# PCB-DISPLAYDOGM1.net
KiCad netlist of a schematic drawn in EAGLE
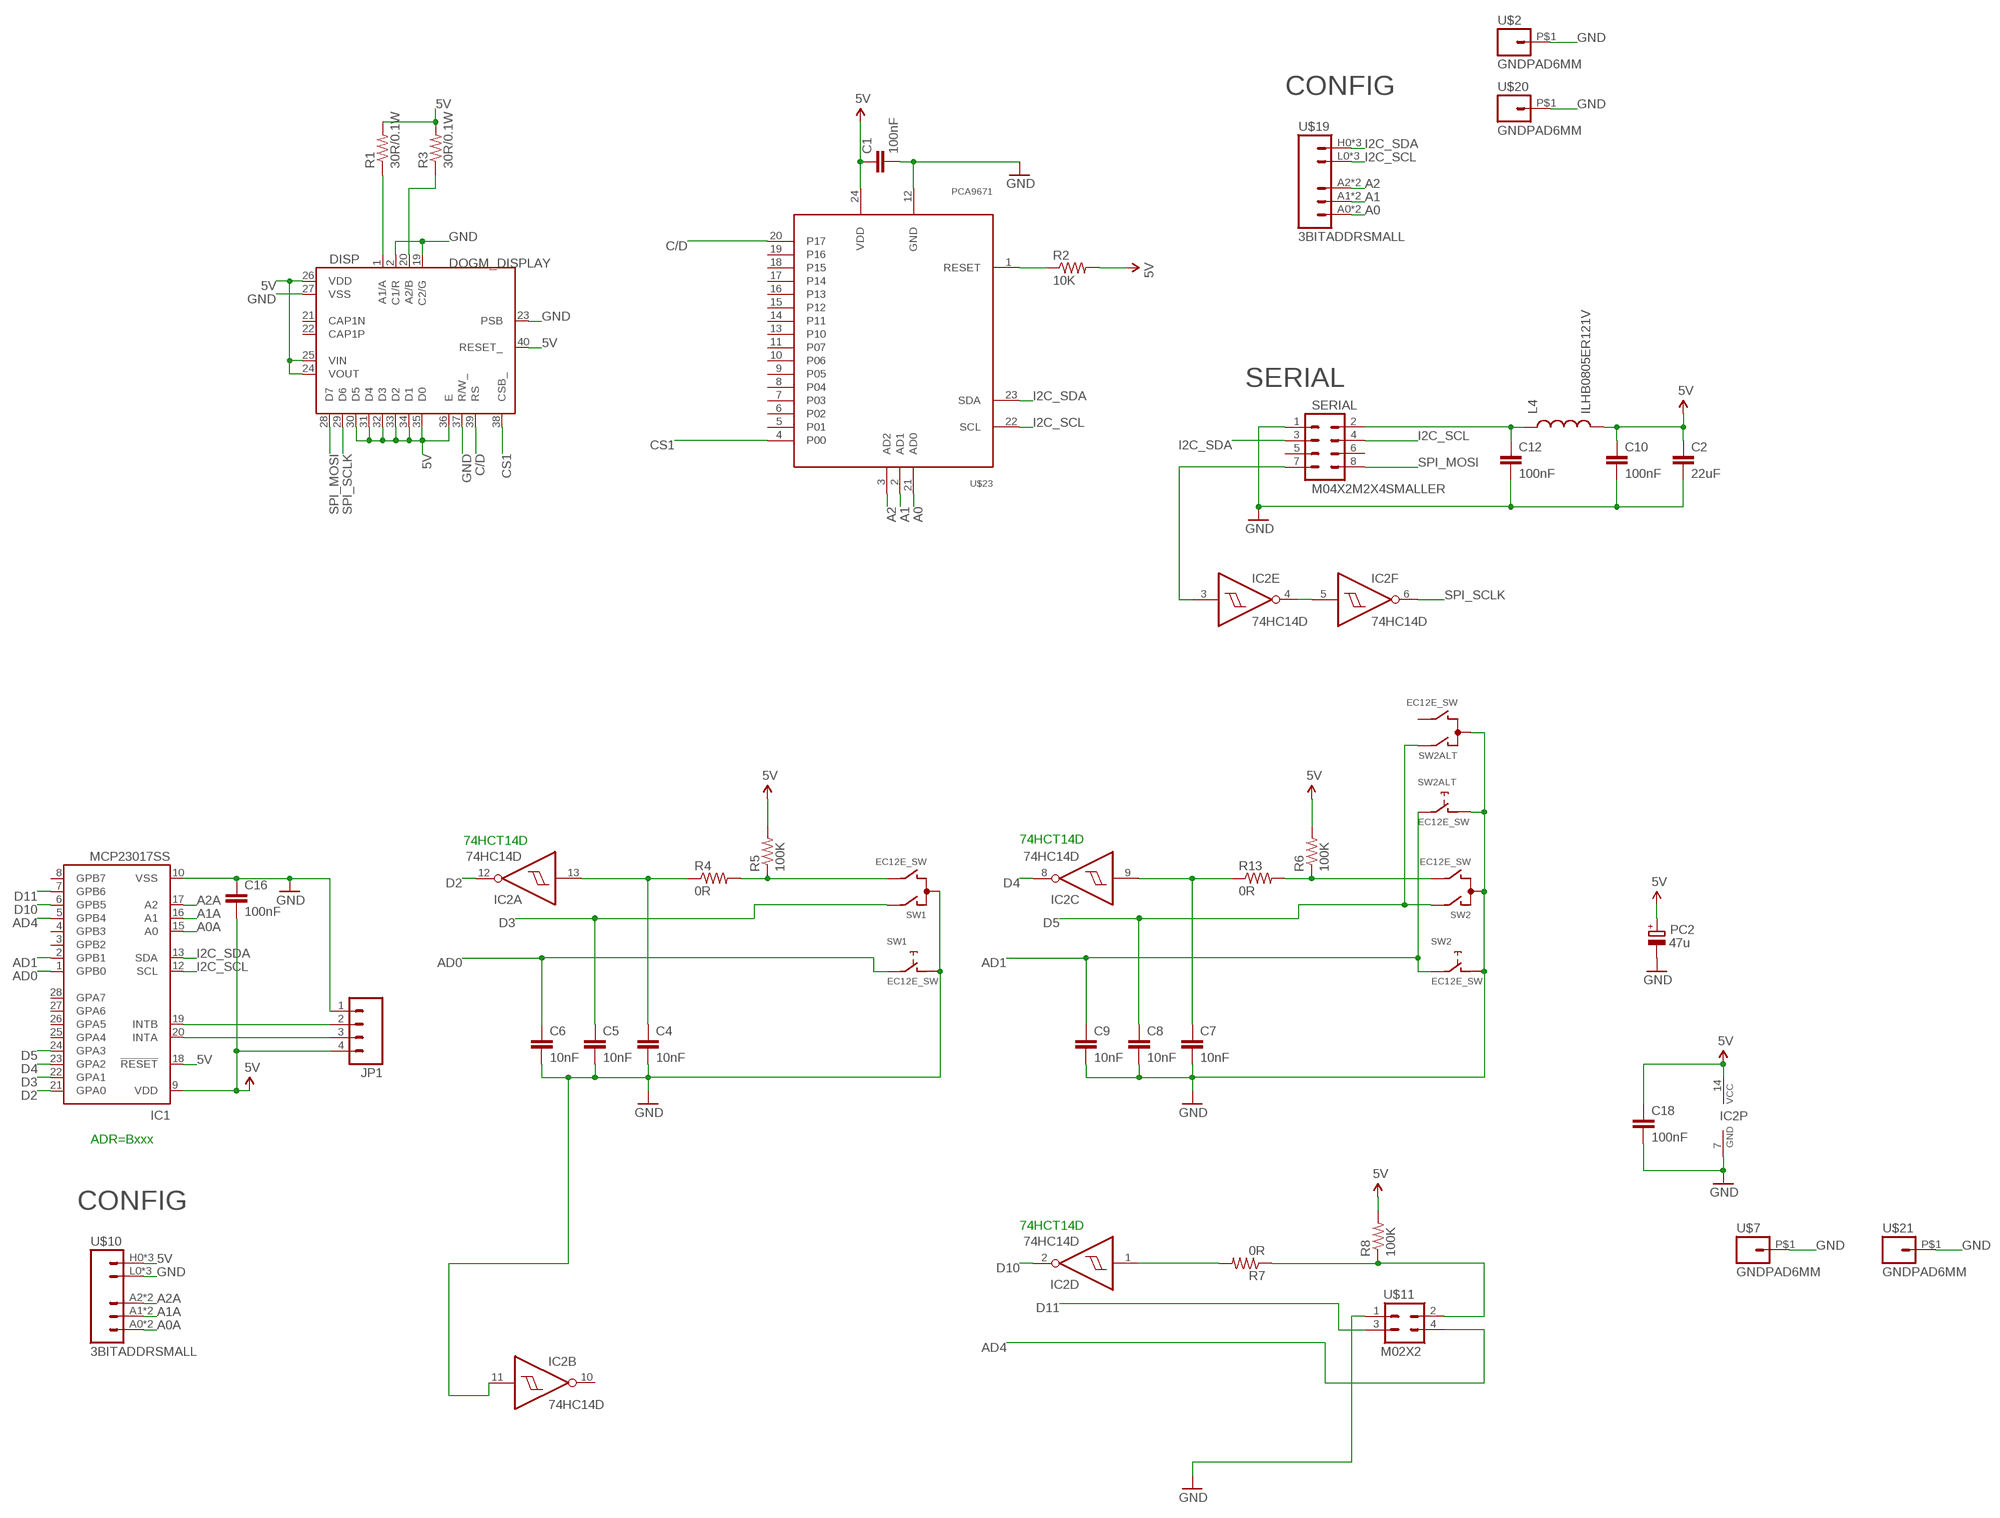
[diagram p0: schematic, sheet 1]

(export (version "E")
  (design (tool "Eeschema 10.0.6"))
  (components
    (comp (ref "C1")
      (value "100nF")
      (footprint "eagle-import:0603-CAP")
      (libsource (lib "eagle-import") (part "CAP0603-CAP"))
    )
    (comp (ref "C2")
      (value "22uF")
      (footprint "eagle-import:0805")
      (libsource (lib "eagle-import") (part "CAP0805"))
    )
    (comp (ref "C4")
      (value "10nF")
      (footprint "eagle-import:0603-CAP")
      (libsource (lib "eagle-import") (part "CAP0603-CAP"))
    )
    (comp (ref "C5")
      (value "10nF")
      (footprint "eagle-import:0603-CAP")
      (libsource (lib "eagle-import") (part "CAP0603-CAP"))
    )
    (comp (ref "C6")
      (value "10nF")
      (footprint "eagle-import:0603-CAP")
      (libsource (lib "eagle-import") (part "CAP0603-CAP"))
    )
    (comp (ref "C7")
      (value "10nF")
      (footprint "eagle-import:0603-CAP")
      (libsource (lib "eagle-import") (part "CAP0603-CAP"))
    )
    (comp (ref "C8")
      (value "10nF")
      (footprint "eagle-import:0603-CAP")
      (libsource (lib "eagle-import") (part "CAP0603-CAP"))
    )
    (comp (ref "C9")
      (value "10nF")
      (footprint "eagle-import:0603-CAP")
      (libsource (lib "eagle-import") (part "CAP0603-CAP"))
    )
    (comp (ref "C10")
      (value "100nF")
      (footprint "eagle-import:0603-CAP")
      (libsource (lib "eagle-import") (part "CAP0603-CAP"))
    )
    (comp (ref "C12")
      (value "100nF")
      (footprint "eagle-import:0603-CAP")
      (libsource (lib "eagle-import") (part "CAP0603-CAP"))
    )
    (comp (ref "C16")
      (value "100nF")
      (footprint "eagle-import:0603-CAP")
      (libsource (lib "eagle-import") (part "CAP0603-CAP"))
    )
    (comp (ref "C18")
      (value "100nF")
      (footprint "eagle-import:0603-CAP")
      (libsource (lib "eagle-import") (part "CAP0603-CAP"))
    )
    (comp (ref "DISP")
      (value "DOGM_DISPLAY")
      (footprint "eagle-import:DOGM")
      (libsource (lib "eagle-import") (part "DOGM_DISPLAY"))
    )
    (comp (ref "IC1")
      (value "MCP23017SS")
      (footprint "eagle-import:SSOP28")
      (fields
        (field (name "MF") "MICROCHIP")
        (field (name "MPN") "MCP23017-E/SS")
        (field (name "MPN_1") "MCP23017-E/SS")
        (field (name "OC_FARNELL") "1467674")
        (field (name "OC_NEWARK") "31K2960")
      )
      (libsource (lib "eagle-import") (part "MCP23017SS"))
    )
    (comp (ref "IC2")
      (value "74HC14D")
      (footprint "eagle-import:SO14")
      (libsource (lib "eagle-import") (part "7414DHC"))
    )
    (comp (ref "JP1")
      (value "M04PTH")
      (footprint "eagle-import:1X04")
      (libsource (lib "eagle-import") (part "M04PTH"))
    )
    (comp (ref "L4")
      (value "ILHB0805ER121V")
      (footprint "eagle-import:0805")
      (libsource (lib "eagle-import") (part "INDUCTOR0805"))
    )
    (comp (ref "PC2")
      (value "47u")
      (footprint "eagle-import:PANASONIC_D")
      (libsource (lib "eagle-import") (part "CPOL-EUD"))
    )
    (comp (ref "R1")
      (value "30R/0.1W")
      (footprint "eagle-import:0603-RES")
      (libsource (lib "eagle-import") (part "RESISTOR0603-RES"))
    )
    (comp (ref "R2")
      (value "10K")
      (footprint "eagle-import:0603-RES")
      (libsource (lib "eagle-import") (part "RESISTOR0603-RES"))
    )
    (comp (ref "R3")
      (value "30R/0.1W")
      (footprint "eagle-import:0603-RES")
      (libsource (lib "eagle-import") (part "RESISTOR0603-RES"))
    )
    (comp (ref "R4")
      (value "0R")
      (footprint "eagle-import:0603-RES")
      (libsource (lib "eagle-import") (part "RESISTOR0603-RES"))
    )
    (comp (ref "R5")
      (value "100K")
      (footprint "eagle-import:0603-RES")
      (libsource (lib "eagle-import") (part "RESISTOR0603-RES"))
    )
    (comp (ref "R6")
      (value "100K")
      (footprint "eagle-import:0603-RES")
      (libsource (lib "eagle-import") (part "RESISTOR0603-RES"))
    )
    (comp (ref "R7")
      (value "0R")
      (footprint "eagle-import:0603-RES")
      (libsource (lib "eagle-import") (part "RESISTOR0603-RES"))
    )
    (comp (ref "R8")
      (value "100K")
      (footprint "eagle-import:0603-RES")
      (libsource (lib "eagle-import") (part "RESISTOR0603-RES"))
    )
    (comp (ref "R13")
      (value "0R")
      (footprint "eagle-import:0603-RES")
      (libsource (lib "eagle-import") (part "RESISTOR0603-RES"))
    )
    (comp (ref "SERIAL")
      (value "M04X2M2X4SMALLER")
      (footprint "eagle-import:M2X4SMALLER")
      (libsource (lib "eagle-import") (part "M04X2M2X4SMALLER"))
    )
    (comp (ref "SW1")
      (value "EC12E_SW")
      (footprint "eagle-import:ALPS_EC12E_SW")
      (fields (field (name "MPN") "EC12E2424407"))
      (libsource (lib "eagle-import") (part "EC12E_SW"))
    )
    (comp (ref "SW2")
      (value "EC12E_SW")
      (footprint "eagle-import:ALPS_EC12E_SW")
      (fields (field (name "MPN") "EC12E2424407"))
      (libsource (lib "eagle-import") (part "EC12E_SW"))
    )
    (comp (ref "SW2ALT")
      (value "EC12E_SW")
      (footprint "eagle-import:ALPS_EC12E_SW")
      (fields (field (name "MPN") "EC12E2424407"))
      (libsource (lib "eagle-import") (part "EC12E_SW"))
    )
    (comp (ref "U$2")
      (value "GNDPAD6MM")
      (footprint "eagle-import:3.2MMPAD6MM")
      (libsource (lib "eagle-import") (part "GNDPAD6MM"))
    )
    (comp (ref "U$7")
      (value "GNDPAD6MM")
      (footprint "eagle-import:3.2MMPAD6MM")
      (libsource (lib "eagle-import") (part "GNDPAD6MM"))
    )
    (comp (ref "U$10")
      (value "3BITADDRSMALL")
      (footprint "eagle-import:3BITADDR_SMALL")
      (libsource (lib "eagle-import") (part "3BITADDRSMALL"))
    )
    (comp (ref "U$11")
      (value "M02X2")
      (footprint "eagle-import:2X2")
      (libsource (lib "eagle-import") (part "M02X2"))
    )
    (comp (ref "U$19")
      (value "3BITADDRSMALL")
      (footprint "eagle-import:3BITADDR_SMALL")
      (libsource (lib "eagle-import") (part "3BITADDRSMALL"))
    )
    (comp (ref "U$20")
      (value "GNDPAD6MM")
      (footprint "eagle-import:3.2MMPAD6MM")
      (libsource (lib "eagle-import") (part "GNDPAD6MM"))
    )
    (comp (ref "U$21")
      (value "GNDPAD6MM")
      (footprint "eagle-import:3.2MMPAD6MM")
      (libsource (lib "eagle-import") (part "GNDPAD6MM"))
    )
    (comp (ref "U$23")
      (value "PCA9671")
      (footprint "eagle-import:TSSOP24")
      (libsource (lib "eagle-import") (part "PCA9671"))
    )
  )
  (nets
    (net (code "1") (name "5V") (class "Default")
      (node (ref "C1") (pin "1") (pinfunction "1_1") (pintype "passive"))
      (node (ref "C10") (pin "1") (pinfunction "1_1") (pintype "passive"))
      (node (ref "C16") (pin "2") (pinfunction "2_2") (pintype "passive"))
      (node (ref "C18") (pin "1") (pinfunction "1_1") (pintype "passive"))
      (node (ref "C2") (pin "1") (pinfunction "1_1") (pintype "passive"))
      (node (ref "DISP") (pin "24") (pinfunction "VOUT_24") (pintype "bidirectional"))
      (node (ref "DISP") (pin "25") (pinfunction "VIN_25") (pintype "bidirectional"))
      (node (ref "DISP") (pin "26") (pinfunction "VDD_26") (pintype "power_in"))
      (node (ref "DISP") (pin "30") (pinfunction "D5_30") (pintype "bidirectional"))
      (node (ref "DISP") (pin "31") (pinfunction "D4_31") (pintype "bidirectional"))
      (node (ref "DISP") (pin "32") (pinfunction "D3_32") (pintype "bidirectional"))
      (node (ref "DISP") (pin "33") (pinfunction "D2_33") (pintype "bidirectional"))
      (node (ref "DISP") (pin "34") (pinfunction "D1_34") (pintype "bidirectional"))
      (node (ref "DISP") (pin "35") (pinfunction "D0_35") (pintype "bidirectional"))
      (node (ref "DISP") (pin "36") (pinfunction "E_36") (pintype "bidirectional"))
      (node (ref "DISP") (pin "40") (pinfunction "RESET__40") (pintype "bidirectional"))
      (node (ref "IC1") (pin "18") (pinfunction "~{RESET}_18") (pintype "input"))
      (node (ref "IC1") (pin "9") (pinfunction "VDD_9") (pintype "power_in"))
      (node (ref "IC2") (pin "14") (pinfunction "VCC_14") (pintype "power_in"))
      (node (ref "JP1") (pin "4") (pinfunction "4_4") (pintype "passive"))
      (node (ref "L4") (pin "2") (pinfunction "2_2") (pintype "passive"))
      (node (ref "PC2") (pin "+") (pinfunction "+_+") (pintype "passive"))
      (node (ref "R1") (pin "2") (pinfunction "2_2") (pintype "passive"))
      (node (ref "R2") (pin "2") (pinfunction "2_2") (pintype "passive"))
      (node (ref "R3") (pin "2") (pinfunction "2_2") (pintype "passive"))
      (node (ref "R5") (pin "2") (pinfunction "2_2") (pintype "passive"))
      (node (ref "R6") (pin "2") (pinfunction "2_2") (pintype "passive"))
      (node (ref "R8") (pin "2") (pinfunction "2_2") (pintype "passive"))
      (node (ref "U$10") (pin "H0") (pinfunction "VCC_H0") (pintype "passive"))
      (node (ref "U$10") (pin "H1") (pinfunction "VCC_H1") (pintype "passive"))
      (node (ref "U$10") (pin "H2") (pinfunction "VCC_H2") (pintype "passive"))
      (node (ref "U$23") (pin "24") (pinfunction "VDD_24") (pintype "power_in"))
    )
    (net (code "2") (name "A0") (class "Default")
      (node (ref "U$19") (pin "A0") (pinfunction "A0_A0") (pintype "passive"))
      (node (ref "U$19") (pin "AS0") (pinfunction "A0_AS0") (pintype "passive"))
      (node (ref "U$23") (pin "21") (pinfunction "AD0_21") (pintype "input"))
    )
    (net (code "3") (name "A0A") (class "Default")
      (node (ref "IC1") (pin "15") (pinfunction "A0_15") (pintype "input"))
      (node (ref "U$10") (pin "A0") (pinfunction "A0_A0") (pintype "passive"))
      (node (ref "U$10") (pin "AS0") (pinfunction "A0_AS0") (pintype "passive"))
    )
    (net (code "4") (name "A1") (class "Default")
      (node (ref "U$19") (pin "A1") (pinfunction "A1_A1") (pintype "passive"))
      (node (ref "U$19") (pin "AS1") (pinfunction "A1_AS1") (pintype "passive"))
      (node (ref "U$23") (pin "2") (pinfunction "AD1_2") (pintype "input"))
    )
    (net (code "5") (name "A1A") (class "Default")
      (node (ref "IC1") (pin "16") (pinfunction "A1_16") (pintype "input"))
      (node (ref "U$10") (pin "A1") (pinfunction "A1_A1") (pintype "passive"))
      (node (ref "U$10") (pin "AS1") (pinfunction "A1_AS1") (pintype "passive"))
    )
    (net (code "6") (name "A2") (class "Default")
      (node (ref "U$19") (pin "A2") (pinfunction "A2_A2") (pintype "passive"))
      (node (ref "U$19") (pin "AS2") (pinfunction "A2_AS2") (pintype "passive"))
      (node (ref "U$23") (pin "3") (pinfunction "AD2_3") (pintype "input"))
    )
    (net (code "7") (name "A2A") (class "Default")
      (node (ref "IC1") (pin "17") (pinfunction "A2_17") (pintype "input"))
      (node (ref "U$10") (pin "A2") (pinfunction "A2_A2") (pintype "passive"))
      (node (ref "U$10") (pin "AS2") (pinfunction "A2_AS2") (pintype "passive"))
    )
    (net (code "8") (name "AD0") (class "Default")
      (node (ref "C6") (pin "1") (pinfunction "1_1") (pintype "passive"))
      (node (ref "IC1") (pin "1") (pinfunction "GPB0_1") (pintype "bidirectional"))
      (node (ref "SW1") (pin "E") (pinfunction "2_E") (pintype "passive"))
    )
    (net (code "9") (name "AD1") (class "Default")
      (node (ref "C9") (pin "1") (pinfunction "1_1") (pintype "passive"))
      (node (ref "IC1") (pin "2") (pinfunction "GPB1_2") (pintype "bidirectional"))
      (node (ref "SW2") (pin "E") (pinfunction "2_E") (pintype "passive"))
      (node (ref "SW2ALT") (pin "E") (pinfunction "2_E") (pintype "passive"))
    )
    (net (code "10") (name "AD4") (class "Default")
      (node (ref "IC1") (pin "5") (pinfunction "GPB4_5") (pintype "bidirectional"))
      (node (ref "U$11") (pin "4") (pinfunction "4_4") (pintype "passive"))
    )
    (net (code "11") (name "CS1") (class "Default")
      (node (ref "DISP") (pin "38") (pinfunction "CSB__38") (pintype "bidirectional"))
      (node (ref "U$23") (pin "4") (pinfunction "P00_4") (pintype "output"))
    )
    (net (code "12") (name "C{slash}D") (class "Default")
      (node (ref "DISP") (pin "39") (pinfunction "RS_39") (pintype "bidirectional"))
      (node (ref "U$23") (pin "20") (pinfunction "P17_20") (pintype "output"))
    )
    (net (code "13") (name "D2") (class "Default")
      (node (ref "IC1") (pin "21") (pinfunction "GPA0_21") (pintype "bidirectional"))
      (node (ref "IC2") (pin "12") (pinfunction "O_12") (pintype "output"))
    )
    (net (code "14") (name "D3") (class "Default")
      (node (ref "C5") (pin "1") (pinfunction "1_1") (pintype "passive"))
      (node (ref "IC1") (pin "22") (pinfunction "GPA1_22") (pintype "bidirectional"))
      (node (ref "SW1") (pin "A") (pinfunction "A_A") (pintype "passive"))
    )
    (net (code "15") (name "D4") (class "Default")
      (node (ref "IC1") (pin "23") (pinfunction "GPA2_23") (pintype "bidirectional"))
      (node (ref "IC2") (pin "8") (pinfunction "O_8") (pintype "output"))
    )
    (net (code "16") (name "D5") (class "Default")
      (node (ref "C8") (pin "1") (pinfunction "1_1") (pintype "passive"))
      (node (ref "IC1") (pin "24") (pinfunction "GPA3_24") (pintype "bidirectional"))
      (node (ref "SW2") (pin "A") (pinfunction "A_A") (pintype "passive"))
      (node (ref "SW2ALT") (pin "A") (pinfunction "A_A") (pintype "passive"))
    )
    (net (code "17") (name "D10") (class "Default")
      (node (ref "IC1") (pin "6") (pinfunction "GPB5_6") (pintype "bidirectional"))
      (node (ref "IC2") (pin "2") (pinfunction "O_2") (pintype "output"))
    )
    (net (code "18") (name "D11") (class "Default")
      (node (ref "IC1") (pin "7") (pinfunction "GPB6_7") (pintype "bidirectional"))
      (node (ref "U$11") (pin "3") (pinfunction "3_3") (pintype "passive"))
    )
    (net (code "19") (name "GND") (class "Default")
      (node (ref "C1") (pin "2") (pinfunction "2_2") (pintype "passive"))
      (node (ref "C10") (pin "2") (pinfunction "2_2") (pintype "passive"))
      (node (ref "C12") (pin "2") (pinfunction "2_2") (pintype "passive"))
      (node (ref "C16") (pin "1") (pinfunction "1_1") (pintype "passive"))
      (node (ref "C18") (pin "2") (pinfunction "2_2") (pintype "passive"))
      (node (ref "C2") (pin "2") (pinfunction "2_2") (pintype "passive"))
      (node (ref "C4") (pin "2") (pinfunction "2_2") (pintype "passive"))
      (node (ref "C5") (pin "2") (pinfunction "2_2") (pintype "passive"))
      (node (ref "C6") (pin "2") (pinfunction "2_2") (pintype "passive"))
      (node (ref "C7") (pin "2") (pinfunction "2_2") (pintype "passive"))
      (node (ref "C8") (pin "2") (pinfunction "2_2") (pintype "passive"))
      (node (ref "C9") (pin "2") (pinfunction "2_2") (pintype "passive"))
      (node (ref "DISP") (pin "19") (pinfunction "C2/G_19") (pintype "bidirectional"))
      (node (ref "DISP") (pin "2") (pinfunction "C1/R_2") (pintype "bidirectional"))
      (node (ref "DISP") (pin "23") (pinfunction "PSB_23") (pintype "bidirectional"))
      (node (ref "DISP") (pin "27") (pinfunction "VSS_27") (pintype "power_in"))
      (node (ref "DISP") (pin "37") (pinfunction "R/W__37") (pintype "bidirectional"))
      (node (ref "IC1") (pin "10") (pinfunction "VSS_10") (pintype "power_in"))
      (node (ref "IC2") (pin "11") (pinfunction "I_11") (pintype "input"))
      (node (ref "IC2") (pin "7") (pinfunction "GND_7") (pintype "power_in"))
      (node (ref "JP1") (pin "1") (pinfunction "1_1") (pintype "passive"))
      (node (ref "PC2") (pin "-") (pinfunction "-_-") (pintype "passive"))
      (node (ref "SERIAL") (pin "1") (pinfunction "1_1") (pintype "passive"))
      (node (ref "SW1") (pin "C") (pinfunction "C_C") (pintype "passive"))
      (node (ref "SW1") (pin "D") (pinfunction "1_D") (pintype "passive"))
      (node (ref "SW2") (pin "C") (pinfunction "C_C") (pintype "passive"))
      (node (ref "SW2") (pin "D") (pinfunction "1_D") (pintype "passive"))
      (node (ref "SW2ALT") (pin "C") (pinfunction "C_C") (pintype "passive"))
      (node (ref "SW2ALT") (pin "D") (pinfunction "1_D") (pintype "passive"))
      (node (ref "U$10") (pin "L0") (pinfunction "GND_L0") (pintype "passive"))
      (node (ref "U$10") (pin "L1") (pinfunction "GND_L1") (pintype "passive"))
      (node (ref "U$10") (pin "L2") (pinfunction "GND_L2") (pintype "passive"))
      (node (ref "U$11") (pin "1") (pinfunction "1_1") (pintype "passive"))
      (node (ref "U$2") (pin "P$1") (pinfunction "1_P$1") (pintype "passive"))
      (node (ref "U$20") (pin "P$1") (pinfunction "1_P$1") (pintype "passive"))
      (node (ref "U$21") (pin "P$1") (pinfunction "1_P$1") (pintype "passive"))
      (node (ref "U$23") (pin "12") (pinfunction "GND_12") (pintype "power_in"))
      (node (ref "U$7") (pin "P$1") (pinfunction "1_P$1") (pintype "passive"))
    )
    (net (code "20") (name "I2C_SCL") (class "Default")
      (node (ref "IC1") (pin "12") (pinfunction "SCL_12") (pintype "input"))
      (node (ref "SERIAL") (pin "4") (pinfunction "4_4") (pintype "passive"))
      (node (ref "U$19") (pin "L0") (pinfunction "GND_L0") (pintype "passive"))
      (node (ref "U$19") (pin "L1") (pinfunction "GND_L1") (pintype "passive"))
      (node (ref "U$19") (pin "L2") (pinfunction "GND_L2") (pintype "passive"))
      (node (ref "U$23") (pin "22") (pinfunction "SCL_22") (pintype "input"))
    )
    (net (code "21") (name "I2C_SDA") (class "Default")
      (node (ref "IC1") (pin "13") (pinfunction "SDA_13") (pintype "bidirectional"))
      (node (ref "SERIAL") (pin "3") (pinfunction "3_3") (pintype "passive"))
      (node (ref "U$19") (pin "H0") (pinfunction "VCC_H0") (pintype "passive"))
      (node (ref "U$19") (pin "H1") (pinfunction "VCC_H1") (pintype "passive"))
      (node (ref "U$19") (pin "H2") (pinfunction "VCC_H2") (pintype "passive"))
      (node (ref "U$23") (pin "23") (pinfunction "SDA_23") (pintype "input"))
    )
    (net (code "22") (name "Net-(C12-Pad1)") (class "Default")
      (node (ref "C12") (pin "1") (pinfunction "1_1") (pintype "passive"))
      (node (ref "L4") (pin "1") (pinfunction "1_1") (pintype "passive"))
      (node (ref "SERIAL") (pin "2") (pinfunction "2_2") (pintype "passive"))
    )
    (net (code "23") (name "Net-(DISP-A1{slash}A)") (class "Default")
      (node (ref "DISP") (pin "1") (pinfunction "A1/A_1") (pintype "bidirectional"))
      (node (ref "R1") (pin "1") (pinfunction "1_1") (pintype "passive"))
    )
    (net (code "24") (name "Net-(DISP-A2{slash}B)") (class "Default")
      (node (ref "DISP") (pin "20") (pinfunction "A2/B_20") (pintype "bidirectional"))
      (node (ref "R3") (pin "1") (pinfunction "1_1") (pintype "passive"))
    )
    (net (code "25") (name "Net-(IC1-INTA)") (class "Default")
      (node (ref "IC1") (pin "20") (pinfunction "INTA_20") (pintype "output"))
      (node (ref "JP1") (pin "3") (pinfunction "3_3") (pintype "passive"))
    )
    (net (code "26") (name "Net-(IC1-INTB)") (class "Default")
      (node (ref "IC1") (pin "19") (pinfunction "INTB_19") (pintype "output"))
      (node (ref "JP1") (pin "2") (pinfunction "2_2") (pintype "passive"))
    )
    (net (code "27") (name "Net-(IC2A-I)") (class "Default")
      (node (ref "C4") (pin "1") (pinfunction "1_1") (pintype "passive"))
      (node (ref "IC2") (pin "13") (pinfunction "I_13") (pintype "input"))
      (node (ref "R4") (pin "1") (pinfunction "1_1") (pintype "passive"))
    )
    (net (code "28") (name "Net-(IC2C-I)") (class "Default")
      (node (ref "C7") (pin "1") (pinfunction "1_1") (pintype "passive"))
      (node (ref "IC2") (pin "9") (pinfunction "I_9") (pintype "input"))
      (node (ref "R13") (pin "1") (pinfunction "1_1") (pintype "passive"))
    )
    (net (code "29") (name "Net-(IC2D-I)") (class "Default")
      (node (ref "IC2") (pin "1") (pinfunction "I_1") (pintype "input"))
      (node (ref "R7") (pin "2") (pinfunction "2_2") (pintype "passive"))
    )
    (net (code "30") (name "Net-(IC2E-I)") (class "Default")
      (node (ref "IC2") (pin "3") (pinfunction "I_3") (pintype "input"))
      (node (ref "SERIAL") (pin "7") (pinfunction "7_7") (pintype "passive"))
    )
    (net (code "31") (name "Net-(IC2E-O)") (class "Default")
      (node (ref "IC2") (pin "4") (pinfunction "O_4") (pintype "output"))
      (node (ref "IC2") (pin "5") (pinfunction "I_5") (pintype "input"))
    )
    (net (code "32") (name "Net-(R4-Pad2)") (class "Default")
      (node (ref "R4") (pin "2") (pinfunction "2_2") (pintype "passive"))
      (node (ref "R5") (pin "1") (pinfunction "1_1") (pintype "passive"))
      (node (ref "SW1") (pin "B") (pinfunction "B_B") (pintype "passive"))
    )
    (net (code "33") (name "Net-(R7-Pad1)") (class "Default")
      (node (ref "R7") (pin "1") (pinfunction "1_1") (pintype "passive"))
      (node (ref "R8") (pin "1") (pinfunction "1_1") (pintype "passive"))
      (node (ref "U$11") (pin "2") (pinfunction "2_2") (pintype "passive"))
    )
    (net (code "34") (name "Net-(R13-Pad2)") (class "Default")
      (node (ref "R13") (pin "2") (pinfunction "2_2") (pintype "passive"))
      (node (ref "R6") (pin "1") (pinfunction "1_1") (pintype "passive"))
      (node (ref "SW2") (pin "B") (pinfunction "B_B") (pintype "passive"))
    )
    (net (code "35") (name "Net-(U$23-RESET)") (class "Default")
      (node (ref "R2") (pin "1") (pinfunction "1_1") (pintype "passive"))
      (node (ref "U$23") (pin "1") (pinfunction "RESET_1") (pintype "input"))
    )
    (net (code "36") (name "SPI_MOSI") (class "Default")
      (node (ref "DISP") (pin "28") (pinfunction "D7_28") (pintype "bidirectional"))
      (node (ref "SERIAL") (pin "8") (pinfunction "8_8") (pintype "passive"))
    )
    (net (code "37") (name "SPI_SCLK") (class "Default")
      (node (ref "DISP") (pin "29") (pinfunction "D6_29") (pintype "bidirectional"))
      (node (ref "IC2") (pin "6") (pinfunction "O_6") (pintype "output"))
    )
    (net (code "38") (name "unconnected-(DISP-CAP1N-Pad21)") (class "Default")
      (node (ref "DISP") (pin "21") (pinfunction "CAP1N_21") (pintype "bidirectional"))
    )
    (net (code "39") (name "unconnected-(DISP-CAP1P-Pad22)") (class "Default")
      (node (ref "DISP") (pin "22") (pinfunction "CAP1P_22") (pintype "bidirectional"))
    )
    (net (code "40") (name "unconnected-(IC1-GPA4-Pad25)") (class "Default")
      (node (ref "IC1") (pin "25") (pinfunction "GPA4_25") (pintype "bidirectional"))
    )
    (net (code "41") (name "unconnected-(IC1-GPA5-Pad26)") (class "Default")
      (node (ref "IC1") (pin "26") (pinfunction "GPA5_26") (pintype "bidirectional"))
    )
    (net (code "42") (name "unconnected-(IC1-GPA6-Pad27)") (class "Default")
      (node (ref "IC1") (pin "27") (pinfunction "GPA6_27") (pintype "bidirectional"))
    )
    (net (code "43") (name "unconnected-(IC1-GPA7-Pad28)") (class "Default")
      (node (ref "IC1") (pin "28") (pinfunction "GPA7_28") (pintype "bidirectional"))
    )
    (net (code "44") (name "unconnected-(IC1-GPB2-Pad3)") (class "Default")
      (node (ref "IC1") (pin "3") (pinfunction "GPB2_3") (pintype "bidirectional"))
    )
    (net (code "45") (name "unconnected-(IC1-GPB3-Pad4)") (class "Default")
      (node (ref "IC1") (pin "4") (pinfunction "GPB3_4") (pintype "bidirectional"))
    )
    (net (code "46") (name "unconnected-(IC1-GPB7-Pad8)") (class "Default")
      (node (ref "IC1") (pin "8") (pinfunction "GPB7_8") (pintype "bidirectional"))
    )
    (net (code "47") (name "unconnected-(IC2B-O-Pad10)") (class "Default")
      (node (ref "IC2") (pin "10") (pinfunction "O_10") (pintype "output"))
    )
    (net (code "48") (name "unconnected-(SERIAL-Pad5)") (class "Default")
      (node (ref "SERIAL") (pin "5") (pinfunction "5_5") (pintype "passive"))
    )
    (net (code "49") (name "unconnected-(SERIAL-Pad6)") (class "Default")
      (node (ref "SERIAL") (pin "6") (pinfunction "6_6") (pintype "passive"))
    )
    (net (code "50") (name "unconnected-(SW2ALT-PadB)") (class "Default")
      (node (ref "SW2ALT") (pin "B") (pinfunction "B_B") (pintype "passive"))
    )
    (net (code "51") (name "unconnected-(U$23-P01-Pad5)") (class "Default")
      (node (ref "U$23") (pin "5") (pinfunction "P01_5") (pintype "output"))
    )
    (net (code "52") (name "unconnected-(U$23-P02-Pad6)") (class "Default")
      (node (ref "U$23") (pin "6") (pinfunction "P02_6") (pintype "output"))
    )
    (net (code "53") (name "unconnected-(U$23-P03-Pad7)") (class "Default")
      (node (ref "U$23") (pin "7") (pinfunction "P03_7") (pintype "output"))
    )
    (net (code "54") (name "unconnected-(U$23-P04-Pad8)") (class "Default")
      (node (ref "U$23") (pin "8") (pinfunction "P04_8") (pintype "output"))
    )
    (net (code "55") (name "unconnected-(U$23-P05-Pad9)") (class "Default")
      (node (ref "U$23") (pin "9") (pinfunction "P05_9") (pintype "output"))
    )
    (net (code "56") (name "unconnected-(U$23-P06-Pad10)") (class "Default")
      (node (ref "U$23") (pin "10") (pinfunction "P06_10") (pintype "output"))
    )
    (net (code "57") (name "unconnected-(U$23-P07-Pad11)") (class "Default")
      (node (ref "U$23") (pin "11") (pinfunction "P07_11") (pintype "output"))
    )
    (net (code "58") (name "unconnected-(U$23-P10-Pad13)") (class "Default")
      (node (ref "U$23") (pin "13") (pinfunction "P10_13") (pintype "output"))
    )
    (net (code "59") (name "unconnected-(U$23-P11-Pad14)") (class "Default")
      (node (ref "U$23") (pin "14") (pinfunction "P11_14") (pintype "output"))
    )
    (net (code "60") (name "unconnected-(U$23-P12-Pad15)") (class "Default")
      (node (ref "U$23") (pin "15") (pinfunction "P12_15") (pintype "output"))
    )
    (net (code "61") (name "unconnected-(U$23-P13-Pad16)") (class "Default")
      (node (ref "U$23") (pin "16") (pinfunction "P13_16") (pintype "output"))
    )
    (net (code "62") (name "unconnected-(U$23-P14-Pad17)") (class "Default")
      (node (ref "U$23") (pin "17") (pinfunction "P14_17") (pintype "output"))
    )
    (net (code "63") (name "unconnected-(U$23-P15-Pad18)") (class "Default")
      (node (ref "U$23") (pin "18") (pinfunction "P15_18") (pintype "output"))
    )
    (net (code "64") (name "unconnected-(U$23-P16-Pad19)") (class "Default")
      (node (ref "U$23") (pin "19") (pinfunction "P16_19") (pintype "output"))
    )
  )
)
